# 467444_130_3_1-R1.net
KiCad netlist of a schematic drawn in Altium Designer
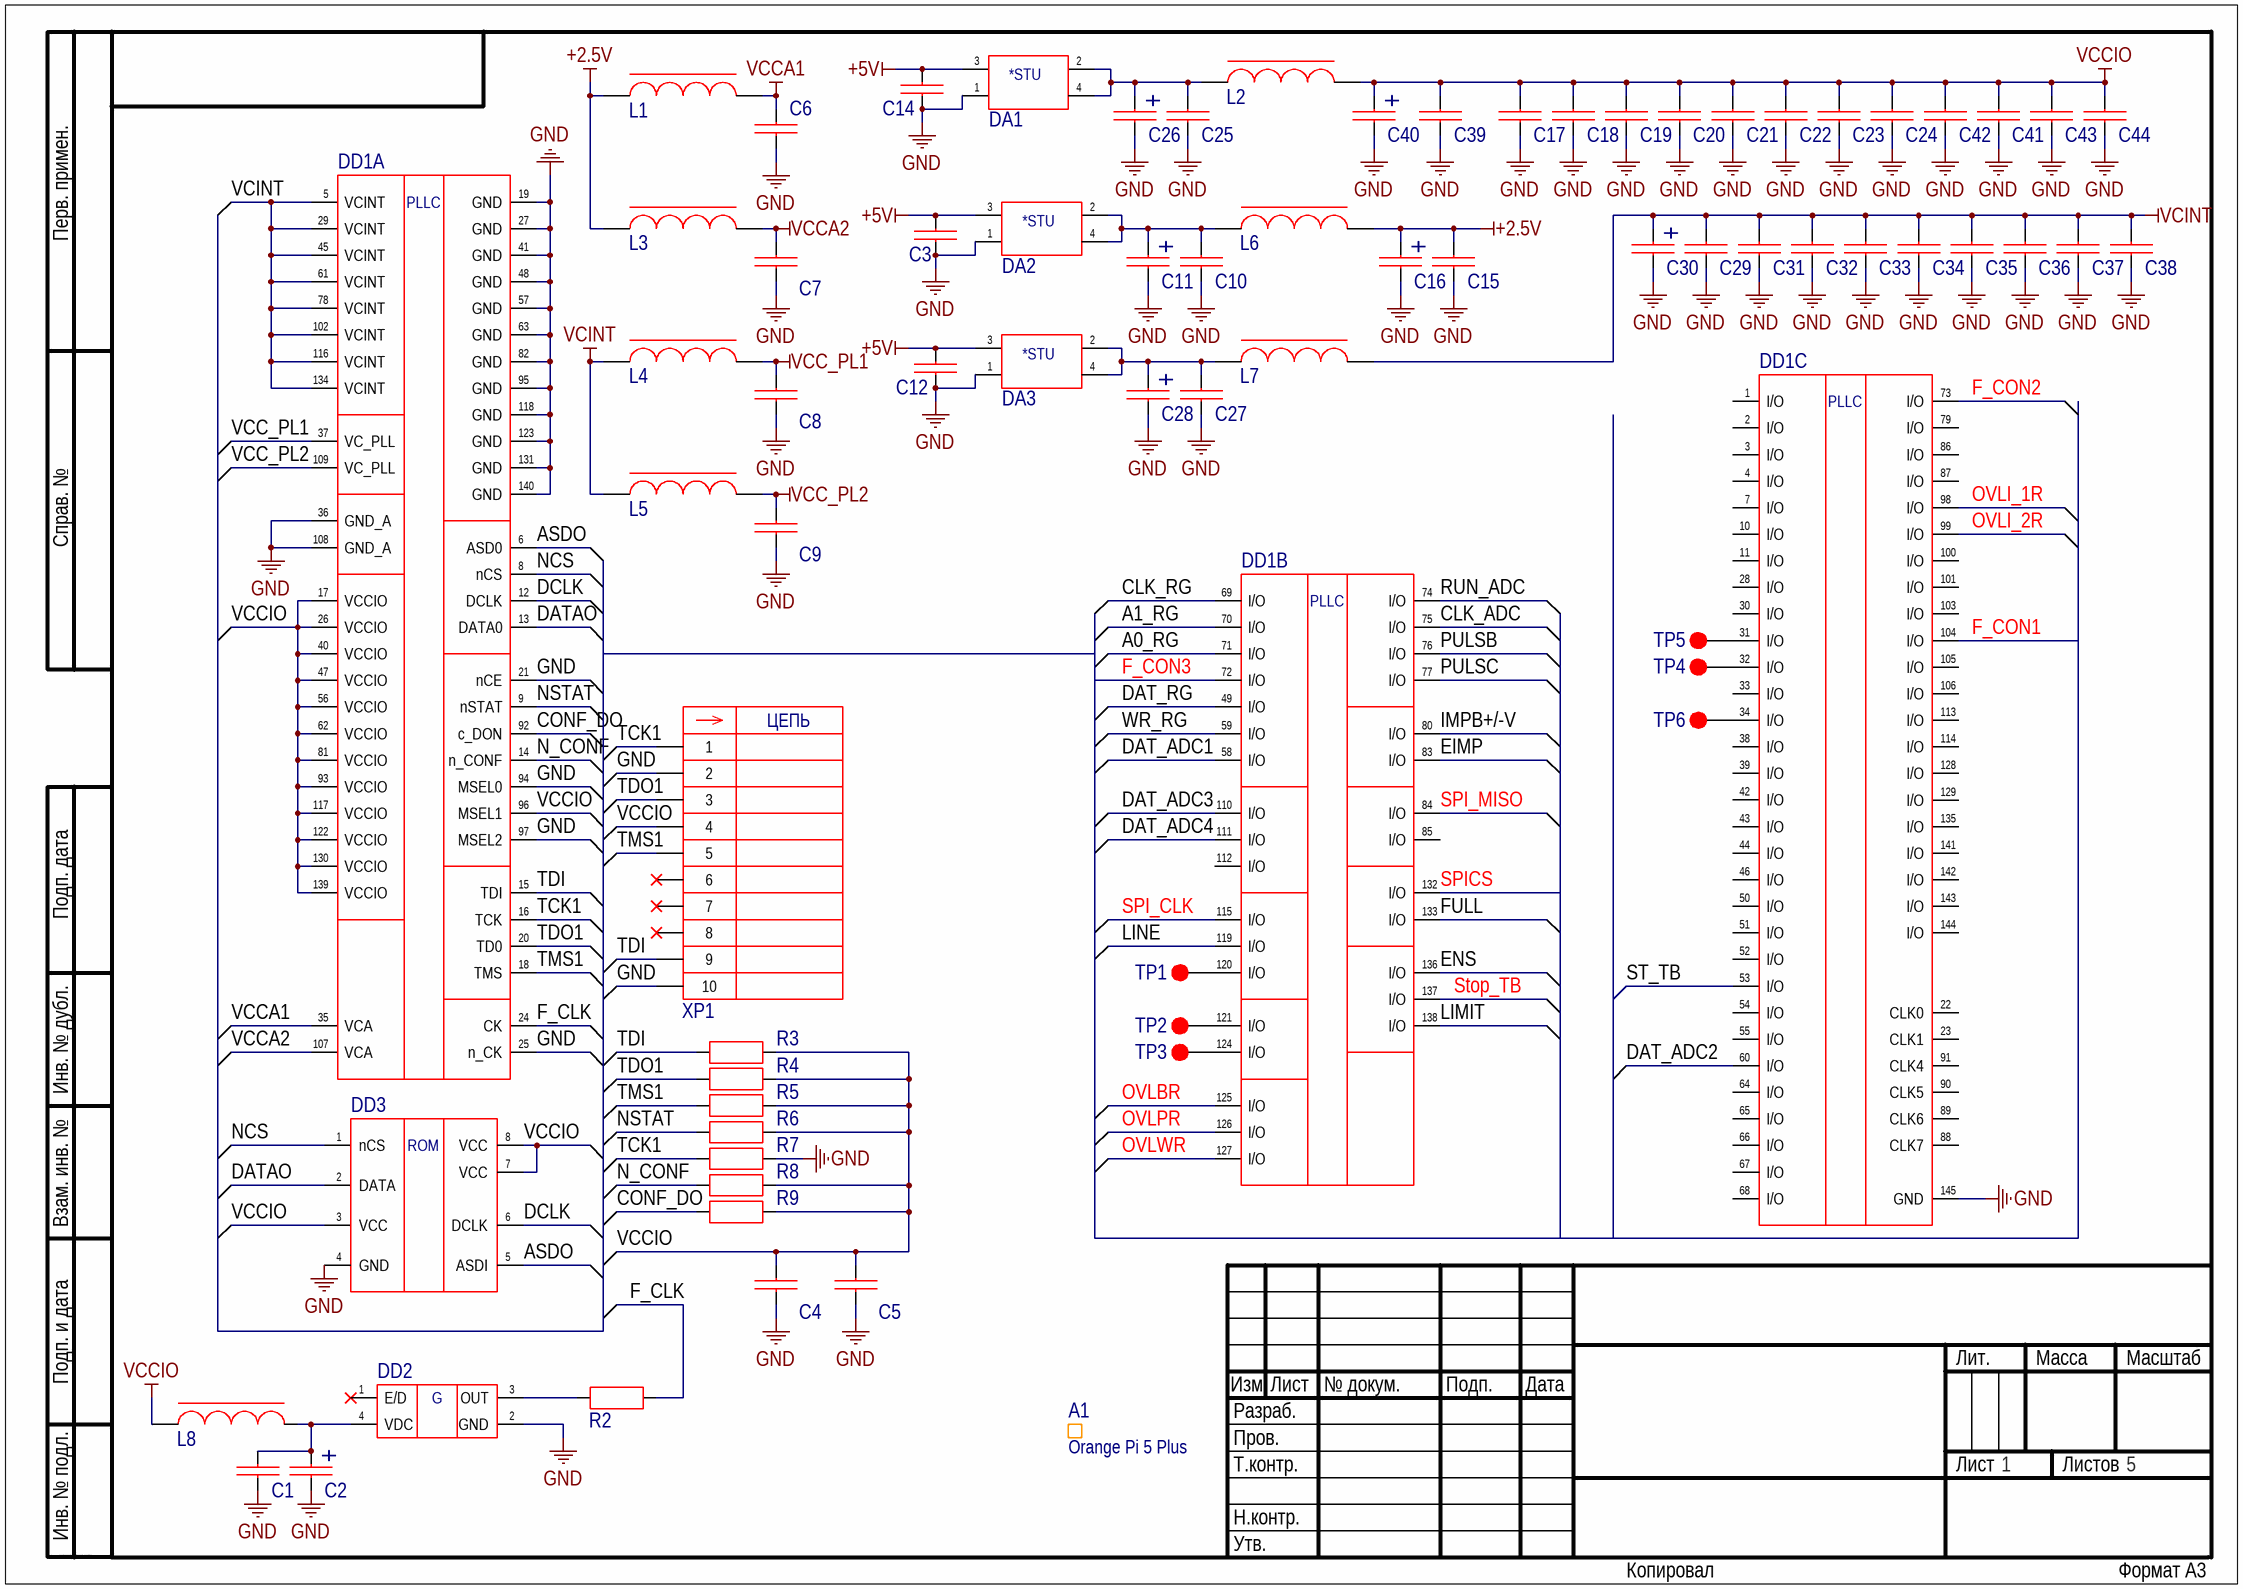
[diagram p0: УШЯИ.467444.130Э3_1-R1.SchDoc]

(export (version "E")
  (design (tool "Eeschema 10.0.6"))
  (components
    (comp (ref "A1")
      (value "Orange Pi 5 Plus")
      (footprint "Orange_Pi_5_Plus")
      (description "8GB Rockchip RK3588, HDMI 2.1, Gigabit LAN port, USB2.0/3.0, microSD card slot, USB Type-C")
      (fields (field (name "MANUFACTURER") "Orange Pi"))
      (libsource (lib "lib") (part "0"))
    )
    (comp (ref "C1")
      (value "0,1 µF")
      (footprint "C_0805 [2012 Metric]")
      (description "Неполярный конденсатор")
      (fields (field (name "MANUFACTURER") "Murata") (field (name "VOLTAGE") "50V"))
      (libsource (lib "lib") (part "C_const"))
    )
    (comp (ref "C2")
      (value "4,7 µF")
      (footprint "C+_1210 [3528-21 Metric]")
      (description "Полярный конденсатор")
      (fields (field (name "MANUFACTURER") "KYOCERA AVX") (field (name "VOLTAGE") "20V\r\n10V"))
      (libsource (lib "lib") (part "C_electrolytic"))
    )
    (comp (ref "C3")
      (value "0,1 µF")
      (footprint "C_0805 [2012 Metric]")
      (description "Неполярный конденсатор")
      (fields (field (name "MANUFACTURER") "Murata") (field (name "VOLTAGE") "50V"))
      (libsource (lib "lib") (part "C_const"))
    )
    (comp (ref "C4")
      (value "1 µF")
      (footprint "C_0805 [2012 Metric]")
      (description "Неполярный конденсатор")
      (fields (field (name "MANUFACTURER") "Murata") (field (name "VOLTAGE") "16V"))
      (libsource (lib "lib") (part "C_const"))
    )
    (comp (ref "C5")
      (value "1 µF")
      (footprint "C_0805 [2012 Metric]")
      (description "Неполярный конденсатор")
      (fields (field (name "MANUFACTURER") "Murata") (field (name "VOLTAGE") "16V"))
      (libsource (lib "lib") (part "C_const"))
    )
    (comp (ref "C6")
      (value "0,1 µF")
      (footprint "C_0805 [2012 Metric]")
      (description "Неполярный конденсатор")
      (fields (field (name "MANUFACTURER") "Murata") (field (name "VOLTAGE") "50V"))
      (libsource (lib "lib") (part "C_const"))
    )
    (comp (ref "C7")
      (value "0,1 µF")
      (footprint "C_0805 [2012 Metric]")
      (description "Неполярный конденсатор")
      (fields (field (name "MANUFACTURER") "Murata") (field (name "VOLTAGE") "50V"))
      (libsource (lib "lib") (part "C_const"))
    )
    (comp (ref "C8")
      (value "0,1 µF")
      (footprint "C_0805 [2012 Metric]")
      (description "Неполярный конденсатор")
      (fields (field (name "MANUFACTURER") "Murata") (field (name "VOLTAGE") "50V"))
      (libsource (lib "lib") (part "C_const"))
    )
    (comp (ref "C9")
      (value "0,1 µF")
      (footprint "C_0805 [2012 Metric]")
      (description "Неполярный конденсатор")
      (fields (field (name "MANUFACTURER") "Murata") (field (name "VOLTAGE") "50V"))
      (libsource (lib "lib") (part "C_const"))
    )
    (comp (ref "C10")
      (value "0,1 µF")
      (footprint "C_0805 [2012 Metric]")
      (description "Неполярный конденсатор")
      (fields (field (name "MANUFACTURER") "Murata") (field (name "VOLTAGE") "50V"))
      (libsource (lib "lib") (part "C_const"))
    )
    (comp (ref "C11")
      (value "4,7 µF")
      (footprint "C+_1210 [3528-21 Metric]")
      (description "Полярный конденсатор")
      (fields (field (name "MANUFACTURER") "KYOCERA AVX") (field (name "VOLTAGE") "20V\r\n10V"))
      (libsource (lib "lib") (part "C_electrolytic"))
    )
    (comp (ref "C12")
      (value "0,1 µF")
      (footprint "C_0805 [2012 Metric]")
      (description "Неполярный конденсатор")
      (fields (field (name "MANUFACTURER") "Murata") (field (name "VOLTAGE") "50V"))
      (libsource (lib "lib") (part "C_const"))
    )
    (comp (ref "C14")
      (value "0,1 µF")
      (footprint "C_0805 [2012 Metric]")
      (description "Неполярный конденсатор")
      (fields (field (name "MANUFACTURER") "Murata") (field (name "VOLTAGE") "50V"))
      (libsource (lib "lib") (part "C_const"))
    )
    (comp (ref "C15")
      (value "0,1 µF")
      (footprint "C_0805 [2012 Metric]")
      (description "Неполярный конденсатор")
      (fields (field (name "MANUFACTURER") "Murata") (field (name "VOLTAGE") "50V"))
      (libsource (lib "lib") (part "C_const"))
    )
    (comp (ref "C16")
      (value "10 µF")
      (footprint "C+_1210 [3528-21 Metric]")
      (description "Полярный конденсатор")
      (fields (field (name "MANUFACTURER") "KYOCERA AVX") (field (name "VOLTAGE") "20V\r\n10V"))
      (libsource (lib "lib") (part "C_electrolytic"))
    )
    (comp (ref "C17")
      (value "0,1 µF")
      (footprint "C_0805 [2012 Metric]")
      (description "Неполярный конденсатор")
      (fields (field (name "MANUFACTURER") "Murata") (field (name "VOLTAGE") "50V"))
      (libsource (lib "lib") (part "C_const"))
    )
    (comp (ref "C18")
      (value "0,1 µF")
      (footprint "C_0805 [2012 Metric]")
      (description "Неполярный конденсатор")
      (fields (field (name "MANUFACTURER") "Murata") (field (name "VOLTAGE") "50V"))
      (libsource (lib "lib") (part "C_const"))
    )
    (comp (ref "C19")
      (value "0,1 µF")
      (footprint "C_0805 [2012 Metric]")
      (description "Неполярный конденсатор")
      (fields (field (name "MANUFACTURER") "Murata") (field (name "VOLTAGE") "50V"))
      (libsource (lib "lib") (part "C_const"))
    )
    (comp (ref "C20")
      (value "0,1 µF")
      (footprint "C_0805 [2012 Metric]")
      (description "Неполярный конденсатор")
      (fields (field (name "MANUFACTURER") "Murata") (field (name "VOLTAGE") "50V"))
      (libsource (lib "lib") (part "C_const"))
    )
    (comp (ref "C21")
      (value "0,1 µF")
      (footprint "C_0805 [2012 Metric]")
      (description "Неполярный конденсатор")
      (fields (field (name "MANUFACTURER") "Murata") (field (name "VOLTAGE") "50V"))
      (libsource (lib "lib") (part "C_const"))
    )
    (comp (ref "C22")
      (value "0,1 µF")
      (footprint "C_0805 [2012 Metric]")
      (description "Неполярный конденсатор")
      (fields (field (name "MANUFACTURER") "Murata") (field (name "VOLTAGE") "50V"))
      (libsource (lib "lib") (part "C_const"))
    )
    (comp (ref "C23")
      (value "0,1 µF")
      (footprint "C_0805 [2012 Metric]")
      (description "Неполярный конденсатор")
      (fields (field (name "MANUFACTURER") "Murata") (field (name "VOLTAGE") "50V"))
      (libsource (lib "lib") (part "C_const"))
    )
    (comp (ref "C24")
      (value "0,1 µF")
      (footprint "C_0805 [2012 Metric]")
      (description "Неполярный конденсатор")
      (fields (field (name "MANUFACTURER") "Murata") (field (name "VOLTAGE") "50V"))
      (libsource (lib "lib") (part "C_const"))
    )
    (comp (ref "C25")
      (value "0,1 µF")
      (footprint "C_0805 [2012 Metric]")
      (description "Неполярный конденсатор")
      (fields (field (name "MANUFACTURER") "Murata") (field (name "VOLTAGE") "50V"))
      (libsource (lib "lib") (part "C_const"))
    )
    (comp (ref "C26")
      (value "4,7 µF")
      (footprint "C+_1210 [3528-21 Metric]")
      (description "Полярный конденсатор")
      (fields (field (name "MANUFACTURER") "KYOCERA AVX") (field (name "VOLTAGE") "20V\r\n10V"))
      (libsource (lib "lib") (part "C_electrolytic"))
    )
    (comp (ref "C27")
      (value "0,1 µF")
      (footprint "C_0805 [2012 Metric]")
      (description "Неполярный конденсатор")
      (fields (field (name "MANUFACTURER") "Murata") (field (name "VOLTAGE") "50V"))
      (libsource (lib "lib") (part "C_const"))
    )
    (comp (ref "C28")
      (value "4,7 µF")
      (footprint "C+_1210 [3528-21 Metric]")
      (description "Полярный конденсатор")
      (fields (field (name "MANUFACTURER") "KYOCERA AVX") (field (name "VOLTAGE") "20V\r\n10V"))
      (libsource (lib "lib") (part "C_electrolytic"))
    )
    (comp (ref "C29")
      (value "0,1 µF")
      (footprint "C_0805 [2012 Metric]")
      (description "Неполярный конденсатор")
      (fields (field (name "MANUFACTURER") "Murata") (field (name "VOLTAGE") "50V"))
      (libsource (lib "lib") (part "C_const"))
    )
    (comp (ref "C30")
      (value "4,7 µF")
      (footprint "C+_1210 [3528-21 Metric]")
      (description "Полярный конденсатор")
      (fields (field (name "MANUFACTURER") "KYOCERA AVX") (field (name "VOLTAGE") "20V\r\n10V"))
      (libsource (lib "lib") (part "C_electrolytic"))
    )
    (comp (ref "C31")
      (value "0,1 µF")
      (footprint "C_0805 [2012 Metric]")
      (description "Неполярный конденсатор")
      (fields (field (name "MANUFACTURER") "Murata") (field (name "VOLTAGE") "50V"))
      (libsource (lib "lib") (part "C_const"))
    )
    (comp (ref "C32")
      (value "0,1 µF")
      (footprint "C_0805 [2012 Metric]")
      (description "Неполярный конденсатор")
      (fields (field (name "MANUFACTURER") "Murata") (field (name "VOLTAGE") "50V"))
      (libsource (lib "lib") (part "C_const"))
    )
    (comp (ref "C33")
      (value "0,1 µF")
      (footprint "C_0805 [2012 Metric]")
      (description "Неполярный конденсатор")
      (fields (field (name "MANUFACTURER") "Murata") (field (name "VOLTAGE") "50V"))
      (libsource (lib "lib") (part "C_const"))
    )
    (comp (ref "C34")
      (value "0,1 µF")
      (footprint "C_0805 [2012 Metric]")
      (description "Неполярный конденсатор")
      (fields (field (name "MANUFACTURER") "Murata") (field (name "VOLTAGE") "50V"))
      (libsource (lib "lib") (part "C_const"))
    )
    (comp (ref "C35")
      (value "0,1 µF")
      (footprint "C_0805 [2012 Metric]")
      (description "Неполярный конденсатор")
      (fields (field (name "MANUFACTURER") "Murata") (field (name "VOLTAGE") "50V"))
      (libsource (lib "lib") (part "C_const"))
    )
    (comp (ref "C36")
      (value "0,1 µF")
      (footprint "C_0805 [2012 Metric]")
      (description "Неполярный конденсатор")
      (fields (field (name "MANUFACTURER") "Murata") (field (name "VOLTAGE") "50V"))
      (libsource (lib "lib") (part "C_const"))
    )
    (comp (ref "C37")
      (value "0,1 µF")
      (footprint "C_0805 [2012 Metric]")
      (description "Неполярный конденсатор")
      (fields (field (name "MANUFACTURER") "Murata") (field (name "VOLTAGE") "50V"))
      (libsource (lib "lib") (part "C_const"))
    )
    (comp (ref "C38")
      (value "0,1 µF")
      (footprint "C_0805 [2012 Metric]")
      (description "Неполярный конденсатор")
      (fields (field (name "MANUFACTURER") "Murata") (field (name "VOLTAGE") "50V"))
      (libsource (lib "lib") (part "C_const"))
    )
    (comp (ref "C39")
      (value "0,1 µF")
      (footprint "C_0805 [2012 Metric]")
      (description "Неполярный конденсатор")
      (fields (field (name "MANUFACTURER") "Murata") (field (name "VOLTAGE") "50V"))
      (libsource (lib "lib") (part "C_const"))
    )
    (comp (ref "C40")
      (value "10 µF")
      (footprint "C+_1210 [3528-21 Metric]")
      (description "Полярный конденсатор")
      (fields (field (name "MANUFACTURER") "KYOCERA AVX") (field (name "VOLTAGE") "20V\r\n10V"))
      (libsource (lib "lib") (part "C_electrolytic"))
    )
    (comp (ref "C41")
      (value "0,1 µF")
      (footprint "C_0805 [2012 Metric]")
      (description "Неполярный конденсатор")
      (fields (field (name "MANUFACTURER") "Murata") (field (name "VOLTAGE") "50V"))
      (libsource (lib "lib") (part "C_const"))
    )
    (comp (ref "C42")
      (value "0,1 µF")
      (footprint "C_0805 [2012 Metric]")
      (description "Неполярный конденсатор")
      (fields (field (name "MANUFACTURER") "Murata") (field (name "VOLTAGE") "50V"))
      (libsource (lib "lib") (part "C_const"))
    )
    (comp (ref "C43")
      (value "0,1 µF")
      (footprint "C_0805 [2012 Metric]")
      (description "Неполярный конденсатор")
      (fields (field (name "MANUFACTURER") "Murata") (field (name "VOLTAGE") "50V"))
      (libsource (lib "lib") (part "C_const"))
    )
    (comp (ref "C44")
      (value "0,1 µF")
      (footprint "C_0805 [2012 Metric]")
      (description "Неполярный конденсатор")
      (fields (field (name "MANUFACTURER") "Murata") (field (name "VOLTAGE") "50V"))
      (libsource (lib "lib") (part "C_const"))
    )
    (comp (ref "DA1")
      (value "LD1117AS33TR")
      (footprint "SOT-223")
      (description "IC, Fixed LDO Voltage Regulator, 5.3V to 10V, 1.15V Dropout, 3.3Vout, 1Aout")
      (fields (field (name "MANUFACTURER") "STMicroelectronics"))
      (libsource (lib "lib") (part "VolReg_LD1117AS33TR"))
    )
    (comp (ref "DA2")
      (value "LD1117AS25TR")
      (footprint "SOT-223")
      (description "IC, Linear Voltage Regulator, 1 Output, 1V Dropout, 2.5Vout, 1Aout")
      (fields (field (name "MANUFACTURER") "STMicroelectronics"))
      (libsource (lib "lib") (part "VolReg_LD1117AS33TR"))
    )
    (comp (ref "DA3")
      (value "LD1117AS12TR")
      (footprint "SOT-223")
      (description "IC, Fixed LDO Voltage Regulator, 1 Output, 1V Dropout, 1.2Vout, 1Aout")
      (fields (field (name "MANUFACTURER") "STMicroelectronics"))
      (libsource (lib "lib") (part "VolReg_LD1117AS33TR"))
    )
    (comp (ref "DD1")
      (value "EP3C5E144I7")
      (footprint "EQFP-144[20x20]_0.5_22x22x1.6")
      (description "IC, Cyclone III, Field Programmable Gate Array (FPGA), 	1.15V to 1.25V, 315 MHz, 94 I/O")
      (fields (field (name "MANUFACTURER") "Intel"))
      (libsource (lib "lib") (part "EP3C5E144I7"))
    )
    (comp (ref "DD2")
      (value "O 20,0-JO32-B-3.3-1-T1-LF")
      (footprint "JO32")
      (description "Crystals, Oscillators, 20 MHz")
      (fields (field (name "MANUFACTURER") "Jauch Quartz GmbH"))
      (libsource (lib "lib") (part "JO32"))
    )
    (comp (ref "DD3")
      (value "EPCS4SI8N")
      (footprint "SOIC-8_1.27_5x4x1.75")
      (description "IC, FPGA Configuration Memory, Flash, 4 Mbit, 40 MHz, JTAG, Serial")
      (fields (field (name "MANUFACTURER") "Intel"))
      (libsource (lib "lib") (part "EPCS4"))
    )
    (comp (ref "L1")
      (value "0,22 μH")
      (footprint "IND_LQH31CN")
      (fields (field (name "MANUFACTURER") "Murata") (field (name "TOLERANCE") "±20%"))
      (libsource (lib "lib") (part "IND_ferromagnetic/ferrite_core"))
    )
    (comp (ref "L2")
      (value "~")
      (footprint "IND_0805 [2012 Metric]")
      (fields (field (name "MANUFACTURER") "Vishay") (field (name "TOLERANCE") "±25%"))
      (libsource (lib "lib") (part "IND_ferromagnetic/ferrite_core"))
    )
    (comp (ref "L3")
      (value "0,22 μH")
      (footprint "IND_LQH31CN")
      (fields (field (name "MANUFACTURER") "Murata") (field (name "TOLERANCE") "±20%"))
      (libsource (lib "lib") (part "IND_ferromagnetic/ferrite_core"))
    )
    (comp (ref "L4")
      (value "0,22 μH")
      (footprint "IND_LQH31CN")
      (fields (field (name "MANUFACTURER") "Murata") (field (name "TOLERANCE") "±20%"))
      (libsource (lib "lib") (part "IND_ferromagnetic/ferrite_core"))
    )
    (comp (ref "L5")
      (value "0,22 μH")
      (footprint "IND_LQH31CN")
      (fields (field (name "MANUFACTURER") "Murata") (field (name "TOLERANCE") "±20%"))
      (libsource (lib "lib") (part "IND_ferromagnetic/ferrite_core"))
    )
    (comp (ref "L6")
      (value "~")
      (footprint "IND_0805 [2012 Metric]")
      (fields (field (name "MANUFACTURER") "Vishay") (field (name "TOLERANCE") "±25%"))
      (libsource (lib "lib") (part "IND_ferromagnetic/ferrite_core"))
    )
    (comp (ref "L7")
      (value "~")
      (footprint "IND_0805 [2012 Metric]")
      (fields (field (name "MANUFACTURER") "Vishay") (field (name "TOLERANCE") "±25%"))
      (libsource (lib "lib") (part "IND_ferromagnetic/ferrite_core"))
    )
    (comp (ref "L8")
      (value "~")
      (footprint "IND_0805 [2012 Metric]")
      (fields (field (name "MANUFACTURER") "Vishay") (field (name "TOLERANCE") "±25%"))
      (libsource (lib "lib") (part "IND_ferromagnetic/ferrite_core"))
    )
    (comp (ref "R2")
      (value "51R")
      (footprint "R_0805 [2012 Metric]")
      (fields (field (name "TOLERANCE") "±5%"))
      (libsource (lib "lib") (part "R_Const"))
    )
    (comp (ref "R3")
      (value "1k")
      (footprint "R_0805 [2012 Metric]")
      (fields (field (name "TOLERANCE") "±5%"))
      (libsource (lib "lib") (part "R_Const"))
    )
    (comp (ref "R4")
      (value "10k")
      (footprint "R_0805 [2012 Metric]")
      (fields (field (name "TOLERANCE") "±5%"))
      (libsource (lib "lib") (part "R_Const"))
    )
    (comp (ref "R5")
      (value "1k")
      (footprint "R_0805 [2012 Metric]")
      (fields (field (name "TOLERANCE") "±5%"))
      (libsource (lib "lib") (part "R_Const"))
    )
    (comp (ref "R6")
      (value "10k")
      (footprint "R_0805 [2012 Metric]")
      (fields (field (name "TOLERANCE") "±5%"))
      (libsource (lib "lib") (part "R_Const"))
    )
    (comp (ref "R7")
      (value "1k")
      (footprint "R_0805 [2012 Metric]")
      (fields (field (name "TOLERANCE") "±5%"))
      (libsource (lib "lib") (part "R_Const"))
    )
    (comp (ref "R8")
      (value "10k")
      (footprint "R_0805 [2012 Metric]")
      (fields (field (name "TOLERANCE") "±5%"))
      (libsource (lib "lib") (part "R_Const"))
    )
    (comp (ref "R9")
      (value "10k")
      (footprint "R_0805 [2012 Metric]")
      (fields (field (name "TOLERANCE") "±5%"))
      (libsource (lib "lib") (part "R_Const"))
    )
    (comp (ref "TP1") (value "~") (footprint "DSP_1.3") (libsource (lib "lib") (part "TP")))
    (comp (ref "TP2") (value "~") (footprint "DSP_1.3") (libsource (lib "lib") (part "TP")))
    (comp (ref "TP3") (value "~") (footprint "DSP_1.3") (libsource (lib "lib") (part "TP")))
    (comp (ref "TP4") (value "~") (footprint "DSP_1.3") (libsource (lib "lib") (part "TP")))
    (comp (ref "TP5") (value "~") (footprint "DSP_1.3") (libsource (lib "lib") (part "TP")))
    (comp (ref "TP6") (value "~") (footprint "DSP_1.3") (libsource (lib "lib") (part "TP")))
    (comp (ref "XP1")
      (value "PLD-10")
      (footprint "PLD-10")
      (description "Male, 10 pins, 2 rows, Vertical")
      (fields (field (name "MANUFACTURER") "Connfly electronic"))
      (libsource (lib "lib") (part "M_10"))
    )
  )
  (nets
    (net (code "1") (name "+2.5V") (class "Default")
      (node (ref "C15") (pin "2") (pinfunction "2_2") (pintype "passive"))
      (node (ref "C16") (pin "+") (pinfunction "+_+") (pintype "passive"))
      (node (ref "L1") (pin "1") (pinfunction "1_1") (pintype "passive"))
      (node (ref "L3") (pin "1") (pinfunction "1_1") (pintype "passive"))
      (node (ref "L6") (pin "2") (pinfunction "2_2") (pintype "passive"))
    )
    (net (code "2") (name "+5V") (class "Default")
      (node (ref "C12") (pin "2") (pinfunction "2_2") (pintype "passive"))
      (node (ref "C14") (pin "2") (pinfunction "2_2") (pintype "passive"))
      (node (ref "C3") (pin "2") (pinfunction "2_2") (pintype "passive"))
      (node (ref "DA1") (pin "3") (pinfunction "VIN_3") (pintype "passive"))
      (node (ref "DA2") (pin "3") (pinfunction "VIN_3") (pintype "passive"))
      (node (ref "DA3") (pin "3") (pinfunction "VIN_3") (pintype "passive"))
    )
    (net (code "3") (name "/A0_RG") (class "Default")
      (node (ref "DD1") (pin "71") (pinfunction "I/O_71") (pintype "passive"))
    )
    (net (code "4") (name "/A1_RG") (class "Default")
      (node (ref "DD1") (pin "70") (pinfunction "I/O_70") (pintype "passive"))
    )
    (net (code "5") (name "/ASDO") (class "Default")
      (node (ref "DD1") (pin "6") (pinfunction "ASD0_6") (pintype "passive"))
      (node (ref "DD3") (pin "5") (pinfunction "ASDI_5") (pintype "passive"))
    )
    (net (code "6") (name "/CLK_ADC") (class "Default")
      (node (ref "DD1") (pin "75") (pinfunction "I/O_75") (pintype "passive"))
    )
    (net (code "7") (name "/CLK_RG") (class "Default")
      (node (ref "DD1") (pin "69") (pinfunction "I/O_69") (pintype "passive"))
    )
    (net (code "8") (name "/CONF_DO") (class "Default")
      (node (ref "DD1") (pin "92") (pinfunction "c_DON_92") (pintype "passive"))
      (node (ref "R9") (pin "1") (pinfunction "1_1") (pintype "passive"))
    )
    (net (code "9") (name "/DATAO") (class "Default")
      (node (ref "DD1") (pin "13") (pinfunction "DATA0_13") (pintype "passive"))
      (node (ref "DD3") (pin "2") (pinfunction "DATA_2") (pintype "passive"))
    )
    (net (code "10") (name "/DAT_ADC1") (class "Default")
      (node (ref "DD1") (pin "58") (pinfunction "I/O_58") (pintype "passive"))
    )
    (net (code "11") (name "/DAT_ADC2") (class "Default")
      (node (ref "DD1") (pin "60") (pinfunction "I/O_60") (pintype "passive"))
    )
    (net (code "12") (name "/DAT_ADC3") (class "Default")
      (node (ref "DD1") (pin "110") (pinfunction "I/O_110") (pintype "passive"))
    )
    (net (code "13") (name "/DAT_ADC4") (class "Default")
      (node (ref "DD1") (pin "111") (pinfunction "I/O_111") (pintype "passive"))
    )
    (net (code "14") (name "/DAT_RG") (class "Default")
      (node (ref "DD1") (pin "49") (pinfunction "I/O_49") (pintype "passive"))
    )
    (net (code "15") (name "/DCLK") (class "Default")
      (node (ref "DD1") (pin "12") (pinfunction "DCLK_12") (pintype "passive"))
      (node (ref "DD3") (pin "6") (pinfunction "DCLK_6") (pintype "passive"))
    )
    (net (code "16") (name "/EIMP") (class "Default")
      (node (ref "DD1") (pin "83") (pinfunction "I/O_83") (pintype "passive"))
    )
    (net (code "17") (name "/ENS") (class "Default")
      (node (ref "DD1") (pin "136") (pinfunction "I/O_136") (pintype "passive"))
    )
    (net (code "18") (name "/FULL") (class "Default")
      (node (ref "DD1") (pin "133") (pinfunction "I/O_133") (pintype "passive"))
    )
    (net (code "19") (name "/F_CLK") (class "Default")
      (node (ref "DD1") (pin "24") (pinfunction "CK_24") (pintype "passive"))
      (node (ref "R2") (pin "2") (pinfunction "2_2") (pintype "passive"))
    )
    (net (code "20") (name "/F_CON1") (class "Default")
      (node (ref "DD1") (pin "104") (pinfunction "I/O_104") (pintype "passive"))
    )
    (net (code "21") (name "/F_CON2") (class "Default")
      (node (ref "DD1") (pin "73") (pinfunction "I/O_73") (pintype "passive"))
    )
    (net (code "22") (name "/F_CON3") (class "Default")
      (node (ref "DD1") (pin "72") (pinfunction "I/O_72") (pintype "passive"))
    )
    (net (code "23") (name "/IMPB+{slash}-V") (class "Default")
      (node (ref "DD1") (pin "80") (pinfunction "I/O_80") (pintype "passive"))
    )
    (net (code "24") (name "/LIMIT") (class "Default")
      (node (ref "DD1") (pin "138") (pinfunction "I/O_138") (pintype "passive"))
    )
    (net (code "25") (name "/LINE") (class "Default")
      (node (ref "DD1") (pin "119") (pinfunction "I/O_119") (pintype "passive"))
    )
    (net (code "26") (name "/NCS") (class "Default")
      (node (ref "DD1") (pin "8") (pinfunction "nCS_8") (pintype "passive"))
      (node (ref "DD3") (pin "1") (pinfunction "nCS_1") (pintype "passive"))
    )
    (net (code "27") (name "/NSTAT") (class "Default")
      (node (ref "DD1") (pin "9") (pinfunction "nSTAT_9") (pintype "passive"))
      (node (ref "R6") (pin "1") (pinfunction "1_1") (pintype "passive"))
    )
    (net (code "28") (name "/N_CONF") (class "Default")
      (node (ref "DD1") (pin "14") (pinfunction "n_CONF_14") (pintype "passive"))
      (node (ref "R8") (pin "1") (pinfunction "1_1") (pintype "passive"))
    )
    (net (code "29") (name "/OVLBR") (class "Default")
      (node (ref "DD1") (pin "125") (pinfunction "I/O_125") (pintype "passive"))
    )
    (net (code "30") (name "/OVLI_1R") (class "Default")
      (node (ref "DD1") (pin "98") (pinfunction "I/O_98") (pintype "passive"))
    )
    (net (code "31") (name "/OVLI_2R") (class "Default")
      (node (ref "DD1") (pin "99") (pinfunction "I/O_99") (pintype "passive"))
    )
    (net (code "32") (name "/OVLPR") (class "Default")
      (node (ref "DD1") (pin "126") (pinfunction "I/O_126") (pintype "passive"))
    )
    (net (code "33") (name "/OVLWR") (class "Default")
      (node (ref "DD1") (pin "127") (pinfunction "I/O_127") (pintype "passive"))
    )
    (net (code "34") (name "/PULSB") (class "Default")
      (node (ref "DD1") (pin "76") (pinfunction "I/O_76") (pintype "passive"))
    )
    (net (code "35") (name "/PULSC") (class "Default")
      (node (ref "DD1") (pin "77") (pinfunction "I/O_77") (pintype "passive"))
    )
    (net (code "36") (name "/RUN_ADC") (class "Default")
      (node (ref "DD1") (pin "74") (pinfunction "I/O_74") (pintype "passive"))
    )
    (net (code "37") (name "/SPICS") (class "Default")
      (node (ref "DD1") (pin "132") (pinfunction "I/O_132") (pintype "passive"))
    )
    (net (code "38") (name "/SPI_CLK") (class "Default")
      (node (ref "DD1") (pin "115") (pinfunction "I/O_115") (pintype "passive"))
    )
    (net (code "39") (name "/SPI_MISO") (class "Default")
      (node (ref "DD1") (pin "84") (pinfunction "I/O_84") (pintype "passive"))
    )
    (net (code "40") (name "/ST_TB") (class "Default")
      (node (ref "DD1") (pin "53") (pinfunction "I/O_53") (pintype "passive"))
    )
    (net (code "41") (name "/Stop_TB") (class "Default")
      (node (ref "DD1") (pin "137") (pinfunction "I/O_137") (pintype "passive"))
    )
    (net (code "42") (name "/TCK1") (class "Default")
      (node (ref "DD1") (pin "16") (pinfunction "TCK_16") (pintype "passive"))
      (node (ref "R7") (pin "1") (pinfunction "1_1") (pintype "passive"))
      (node (ref "XP1") (pin "1") (pinfunction "1_1") (pintype "passive"))
    )
    (net (code "43") (name "/TDI") (class "Default")
      (node (ref "DD1") (pin "15") (pinfunction "TDI_15") (pintype "passive"))
      (node (ref "R3") (pin "1") (pinfunction "1_1") (pintype "passive"))
      (node (ref "XP1") (pin "9") (pinfunction "9_9") (pintype "passive"))
    )
    (net (code "44") (name "/TDO1") (class "Default")
      (node (ref "DD1") (pin "20") (pinfunction "TD0_20") (pintype "passive"))
      (node (ref "R4") (pin "1") (pinfunction "1_1") (pintype "passive"))
      (node (ref "XP1") (pin "3") (pinfunction "3_3") (pintype "passive"))
    )
    (net (code "45") (name "/TMS1") (class "Default")
      (node (ref "DD1") (pin "18") (pinfunction "TMS_18") (pintype "passive"))
      (node (ref "R5") (pin "1") (pinfunction "1_1") (pintype "passive"))
      (node (ref "XP1") (pin "5") (pinfunction "5_5") (pintype "passive"))
    )
    (net (code "46") (name "/WR_RG") (class "Default")
      (node (ref "DD1") (pin "59") (pinfunction "I/O_59") (pintype "passive"))
    )
    (net (code "47") (name "GND") (class "Default")
      (node (ref "C1") (pin "1") (pinfunction "1_1") (pintype "passive"))
      (node (ref "C10") (pin "1") (pinfunction "1_1") (pintype "passive"))
      (node (ref "C11") (pin "-") (pinfunction "-_-") (pintype "passive"))
      (node (ref "C12") (pin "1") (pinfunction "1_1") (pintype "passive"))
      (node (ref "C14") (pin "1") (pinfunction "1_1") (pintype "passive"))
      (node (ref "C15") (pin "1") (pinfunction "1_1") (pintype "passive"))
      (node (ref "C16") (pin "-") (pinfunction "-_-") (pintype "passive"))
      (node (ref "C17") (pin "1") (pinfunction "1_1") (pintype "passive"))
      (node (ref "C18") (pin "1") (pinfunction "1_1") (pintype "passive"))
      (node (ref "C19") (pin "1") (pinfunction "1_1") (pintype "passive"))
      (node (ref "C2") (pin "-") (pinfunction "-_-") (pintype "passive"))
      (node (ref "C20") (pin "1") (pinfunction "1_1") (pintype "passive"))
      (node (ref "C21") (pin "1") (pinfunction "1_1") (pintype "passive"))
      (node (ref "C22") (pin "1") (pinfunction "1_1") (pintype "passive"))
      (node (ref "C23") (pin "1") (pinfunction "1_1") (pintype "passive"))
      (node (ref "C24") (pin "1") (pinfunction "1_1") (pintype "passive"))
      (node (ref "C25") (pin "1") (pinfunction "1_1") (pintype "passive"))
      (node (ref "C26") (pin "-") (pinfunction "-_-") (pintype "passive"))
      (node (ref "C27") (pin "1") (pinfunction "1_1") (pintype "passive"))
      (node (ref "C28") (pin "-") (pinfunction "-_-") (pintype "passive"))
      (node (ref "C29") (pin "1") (pinfunction "1_1") (pintype "passive"))
      (node (ref "C3") (pin "1") (pinfunction "1_1") (pintype "passive"))
      (node (ref "C30") (pin "-") (pinfunction "-_-") (pintype "passive"))
      (node (ref "C31") (pin "1") (pinfunction "1_1") (pintype "passive"))
      (node (ref "C32") (pin "1") (pinfunction "1_1") (pintype "passive"))
      (node (ref "C33") (pin "1") (pinfunction "1_1") (pintype "passive"))
      (node (ref "C34") (pin "1") (pinfunction "1_1") (pintype "passive"))
      (node (ref "C35") (pin "1") (pinfunction "1_1") (pintype "passive"))
      (node (ref "C36") (pin "1") (pinfunction "1_1") (pintype "passive"))
      (node (ref "C37") (pin "1") (pinfunction "1_1") (pintype "passive"))
      (node (ref "C38") (pin "1") (pinfunction "1_1") (pintype "passive"))
      (node (ref "C39") (pin "1") (pinfunction "1_1") (pintype "passive"))
      (node (ref "C4") (pin "1") (pinfunction "1_1") (pintype "passive"))
      (node (ref "C40") (pin "-") (pinfunction "-_-") (pintype "passive"))
      (node (ref "C41") (pin "1") (pinfunction "1_1") (pintype "passive"))
      (node (ref "C42") (pin "1") (pinfunction "1_1") (pintype "passive"))
      (node (ref "C43") (pin "1") (pinfunction "1_1") (pintype "passive"))
      (node (ref "C44") (pin "1") (pinfunction "1_1") (pintype "passive"))
      (node (ref "C5") (pin "1") (pinfunction "1_1") (pintype "passive"))
      (node (ref "C6") (pin "1") (pinfunction "1_1") (pintype "passive"))
      (node (ref "C7") (pin "1") (pinfunction "1_1") (pintype "passive"))
      (node (ref "C8") (pin "1") (pinfunction "1_1") (pintype "passive"))
      (node (ref "C9") (pin "1") (pinfunction "1_1") (pintype "passive"))
      (node (ref "DA1") (pin "1") (pinfunction "ADJ/GND_1") (pintype "passive"))
      (node (ref "DA2") (pin "1") (pinfunction "ADJ/GND_1") (pintype "passive"))
      (node (ref "DA3") (pin "1") (pinfunction "ADJ/GND_1") (pintype "passive"))
      (node (ref "DD1") (pin "108") (pinfunction "GND_A_108") (pintype "passive"))
      (node (ref "DD1") (pin "118") (pinfunction "GND_118") (pintype "passive"))
      (node (ref "DD1") (pin "123") (pinfunction "GND_123") (pintype "passive"))
      (node (ref "DD1") (pin "131") (pinfunction "GND_131") (pintype "passive"))
      (node (ref "DD1") (pin "140") (pinfunction "GND_140") (pintype "passive"))
      (node (ref "DD1") (pin "145") (pinfunction "GND_145") (pintype "passive"))
      (node (ref "DD1") (pin "19") (pinfunction "GND_19") (pintype "passive"))
      (node (ref "DD1") (pin "21") (pinfunction "nCE_21") (pintype "passive"))
      (node (ref "DD1") (pin "25") (pinfunction "n_CK_25") (pintype "passive"))
      (node (ref "DD1") (pin "27") (pinfunction "GND_27") (pintype "passive"))
      (node (ref "DD1") (pin "36") (pinfunction "GND_A_36") (pintype "passive"))
      (node (ref "DD1") (pin "41") (pinfunction "GND_41") (pintype "passive"))
      (node (ref "DD1") (pin "48") (pinfunction "GND_48") (pintype "passive"))
      (node (ref "DD1") (pin "57") (pinfunction "GND_57") (pintype "passive"))
      (node (ref "DD1") (pin "63") (pinfunction "GND_63") (pintype "passive"))
      (node (ref "DD1") (pin "82") (pinfunction "GND_82") (pintype "passive"))
      (node (ref "DD1") (pin "94") (pinfunction "MSEL0_94") (pintype "passive"))
      (node (ref "DD1") (pin "95") (pinfunction "GND_95") (pintype "passive"))
      (node (ref "DD1") (pin "97") (pinfunction "MSEL2_97") (pintype "passive"))
      (node (ref "DD2") (pin "2") (pinfunction "GND_2") (pintype "passive"))
      (node (ref "DD3") (pin "4") (pinfunction "GND_4") (pintype "passive"))
      (node (ref "R7") (pin "2") (pinfunction "2_2") (pintype "passive"))
      (node (ref "XP1") (pin "10") (pinfunction "10_10") (pintype "passive"))
      (node (ref "XP1") (pin "2") (pinfunction "2_2") (pintype "passive"))
    )
    (net (code "48") (name "Net-(C10-Pad2)") (class "Default")
      (node (ref "C10") (pin "2") (pinfunction "2_2") (pintype "passive"))
      (node (ref "C11") (pin "+") (pinfunction "+_+") (pintype "passive"))
      (node (ref "DA2") (pin "2") (pinfunction "VOUT_2") (pintype "passive"))
      (node (ref "DA2") (pin "4") (pinfunction "VOUT_4") (pintype "passive"))
      (node (ref "L6") (pin "1") (pinfunction "1_1") (pintype "passive"))
    )
    (net (code "49") (name "Net-(C25-Pad2)") (class "Default")
      (node (ref "C25") (pin "2") (pinfunction "2_2") (pintype "passive"))
      (node (ref "C26") (pin "+") (pinfunction "+_+") (pintype "passive"))
      (node (ref "DA1") (pin "2") (pinfunction "VOUT_2") (pintype "passive"))
      (node (ref "DA1") (pin "4") (pinfunction "VOUT_4") (pintype "passive"))
      (node (ref "L2") (pin "1") (pinfunction "1_1") (pintype "passive"))
    )
    (net (code "50") (name "Net-(C27-Pad2)") (class "Default")
      (node (ref "C27") (pin "2") (pinfunction "2_2") (pintype "passive"))
      (node (ref "C28") (pin "+") (pinfunction "+_+") (pintype "passive"))
      (node (ref "DA3") (pin "2") (pinfunction "VOUT_2") (pintype "passive"))
      (node (ref "DA3") (pin "4") (pinfunction "VOUT_4") (pintype "passive"))
      (node (ref "L7") (pin "1") (pinfunction "1_1") (pintype "passive"))
    )
    (net (code "51") (name "Net-(DD1B-I{slash}O-Pad120)") (class "Default")
      (node (ref "DD1") (pin "120") (pinfunction "I/O_120") (pintype "passive"))
      (node (ref "TP1") (pin "1") (pinfunction "1_1") (pintype "passive"))
    )
    (net (code "52") (name "Net-(DD1B-I{slash}O-Pad121)") (class "Default")
      (node (ref "DD1") (pin "121") (pinfunction "I/O_121") (pintype "passive"))
      (node (ref "TP2") (pin "1") (pinfunction "1_1") (pintype "passive"))
    )
    (net (code "53") (name "Net-(DD1B-I{slash}O-Pad124)") (class "Default")
      (node (ref "DD1") (pin "124") (pinfunction "I/O_124") (pintype "passive"))
      (node (ref "TP3") (pin "1") (pinfunction "1_1") (pintype "passive"))
    )
    (net (code "54") (name "Net-(DD1C-I{slash}O-Pad31)") (class "Default")
      (node (ref "DD1") (pin "31") (pinfunction "I/O_31") (pintype "passive"))
      (node (ref "TP5") (pin "1") (pinfunction "1_1") (pintype "passive"))
    )
    (net (code "55") (name "Net-(DD1C-I{slash}O-Pad32)") (class "Default")
      (node (ref "DD1") (pin "32") (pinfunction "I/O_32") (pintype "passive"))
      (node (ref "TP4") (pin "1") (pinfunction "1_1") (pintype "passive"))
    )
    (net (code "56") (name "Net-(DD1C-I{slash}O-Pad34)") (class "Default")
      (node (ref "DD1") (pin "34") (pinfunction "I/O_34") (pintype "passive"))
      (node (ref "TP6") (pin "1") (pinfunction "1_1") (pintype "passive"))
    )
    (net (code "57") (name "Net-(DD2-OUT)") (class "Default")
      (node (ref "DD2") (pin "3") (pinfunction "OUT_3") (pintype "passive"))
      (node (ref "R2") (pin "1") (pinfunction "1_1") (pintype "passive"))
    )
    (net (code "58") (name "Net-(DD2-VDC)") (class "Default")
      (node (ref "C1") (pin "2") (pinfunction "2_2") (pintype "passive"))
      (node (ref "C2") (pin "+") (pinfunction "+_+") (pintype "passive"))
      (node (ref "DD2") (pin "4") (pinfunction "VDC_4") (pintype "passive"))
      (node (ref "L8") (pin "2") (pinfunction "2_2") (pintype "passive"))
    )
    (net (code "59") (name "VCCA1") (class "Default")
      (node (ref "C6") (pin "2") (pinfunction "2_2") (pintype "passive"))
      (node (ref "DD1") (pin "35") (pinfunction "VCA_35") (pintype "passive"))
      (node (ref "L1") (pin "2") (pinfunction "2_2") (pintype "passive"))
    )
    (net (code "60") (name "VCCA2") (class "Default")
      (node (ref "C7") (pin "2") (pinfunction "2_2") (pintype "passive"))
      (node (ref "DD1") (pin "107") (pinfunction "VCA_107") (pintype "passive"))
      (node (ref "L3") (pin "2") (pinfunction "2_2") (pintype "passive"))
    )
    (net (code "61") (name "VCCIO") (class "Default")
      (node (ref "C17") (pin "2") (pinfunction "2_2") (pintype "passive"))
      (node (ref "C18") (pin "2") (pinfunction "2_2") (pintype "passive"))
      (node (ref "C19") (pin "2") (pinfunction "2_2") (pintype "passive"))
      (node (ref "C20") (pin "2") (pinfunction "2_2") (pintype "passive"))
      (node (ref "C21") (pin "2") (pinfunction "2_2") (pintype "passive"))
      (node (ref "C22") (pin "2") (pinfunction "2_2") (pintype "passive"))
      (node (ref "C23") (pin "2") (pinfunction "2_2") (pintype "passive"))
      (node (ref "C24") (pin "2") (pinfunction "2_2") (pintype "passive"))
      (node (ref "C39") (pin "2") (pinfunction "2_2") (pintype "passive"))
      (node (ref "C4") (pin "2") (pinfunction "2_2") (pintype "passive"))
      (node (ref "C40") (pin "+") (pinfunction "+_+") (pintype "passive"))
      (node (ref "C41") (pin "2") (pinfunction "2_2") (pintype "passive"))
      (node (ref "C42") (pin "2") (pinfunction "2_2") (pintype "passive"))
      (node (ref "C43") (pin "2") (pinfunction "2_2") (pintype "passive"))
      (node (ref "C44") (pin "2") (pinfunction "2_2") (pintype "passive"))
      (node (ref "C5") (pin "2") (pinfunction "2_2") (pintype "passive"))
      (node (ref "DD1") (pin "117") (pinfunction "VCCIO_117") (pintype "passive"))
      (node (ref "DD1") (pin "122") (pinfunction "VCCIO_122") (pintype "passive"))
      (node (ref "DD1") (pin "130") (pinfunction "VCCIO_130") (pintype "passive"))
      (node (ref "DD1") (pin "139") (pinfunction "VCCIO_139") (pintype "passive"))
      (node (ref "DD1") (pin "17") (pinfunction "VCCIO_17") (pintype "passive"))
      (node (ref "DD1") (pin "26") (pinfunction "VCCIO_26") (pintype "passive"))
      (node (ref "DD1") (pin "40") (pinfunction "VCCIO_40") (pintype "passive"))
      (node (ref "DD1") (pin "47") (pinfunction "VCCIO_47") (pintype "passive"))
      (node (ref "DD1") (pin "56") (pinfunction "VCCIO_56") (pintype "passive"))
      (node (ref "DD1") (pin "62") (pinfunction "VCCIO_62") (pintype "passive"))
      (node (ref "DD1") (pin "81") (pinfunction "VCCIO_81") (pintype "passive"))
      (node (ref "DD1") (pin "93") (pinfunction "VCCIO_93") (pintype "passive"))
      (node (ref "DD1") (pin "96") (pinfunction "MSEL1_96") (pintype "passive"))
      (node (ref "DD3") (pin "3") (pinfunction "VCC_3") (pintype "passive"))
      (node (ref "DD3") (pin "7") (pinfunction "VCC_7") (pintype "passive"))
      (node (ref "DD3") (pin "8") (pinfunction "VCC_8") (pintype "passive"))
      (node (ref "L2") (pin "2") (pinfunction "2_2") (pintype "passive"))
      (node (ref "L8") (pin "1") (pinfunction "1_1") (pintype "passive"))
      (node (ref "R3") (pin "2") (pinfunction "2_2") (pintype "passive"))
      (node (ref "R4") (pin "2") (pinfunction "2_2") (pintype "passive"))
      (node (ref "R5") (pin "2") (pinfunction "2_2") (pintype "passive"))
      (node (ref "R6") (pin "2") (pinfunction "2_2") (pintype "passive"))
      (node (ref "R8") (pin "2") (pinfunction "2_2") (pintype "passive"))
      (node (ref "R9") (pin "2") (pinfunction "2_2") (pintype "passive"))
      (node (ref "XP1") (pin "4") (pinfunction "4_4") (pintype "passive"))
    )
    (net (code "62") (name "VCC_PL1") (class "Default")
      (node (ref "C8") (pin "2") (pinfunction "2_2") (pintype "passive"))
      (node (ref "DD1") (pin "37") (pinfunction "VC_PLL_37") (pintype "passive"))
      (node (ref "L4") (pin "2") (pinfunction "2_2") (pintype "passive"))
    )
    (net (code "63") (name "VCC_PL2") (class "Default")
      (node (ref "C9") (pin "2") (pinfunction "2_2") (pintype "passive"))
      (node (ref "DD1") (pin "109") (pinfunction "VC_PLL_109") (pintype "passive"))
      (node (ref "L5") (pin "2") (pinfunction "2_2") (pintype "passive"))
    )
    (net (code "64") (name "VCINT") (class "Default")
      (node (ref "C29") (pin "2") (pinfunction "2_2") (pintype "passive"))
      (node (ref "C30") (pin "+") (pinfunction "+_+") (pintype "passive"))
      (node (ref "C31") (pin "2") (pinfunction "2_2") (pintype "passive"))
      (node (ref "C32") (pin "2") (pinfunction "2_2") (pintype "passive"))
      (node (ref "C33") (pin "2") (pinfunction "2_2") (pintype "passive"))
      (node (ref "C34") (pin "2") (pinfunction "2_2") (pintype "passive"))
      (node (ref "C35") (pin "2") (pinfunction "2_2") (pintype "passive"))
      (node (ref "C36") (pin "2") (pinfunction "2_2") (pintype "passive"))
      (node (ref "C37") (pin "2") (pinfunction "2_2") (pintype "passive"))
      (node (ref "C38") (pin "2") (pinfunction "2_2") (pintype "passive"))
      (node (ref "DD1") (pin "102") (pinfunction "VCINT_102") (pintype "passive"))
      (node (ref "DD1") (pin "116") (pinfunction "VCINT_116") (pintype "passive"))
      (node (ref "DD1") (pin "134") (pinfunction "VCINT_134") (pintype "passive"))
      (node (ref "DD1") (pin "29") (pinfunction "VCINT_29") (pintype "passive"))
      (node (ref "DD1") (pin "45") (pinfunction "VCINT_45") (pintype "passive"))
      (node (ref "DD1") (pin "5") (pinfunction "VCINT_5") (pintype "passive"))
      (node (ref "DD1") (pin "61") (pinfunction "VCINT_61") (pintype "passive"))
      (node (ref "DD1") (pin "78") (pinfunction "VCINT_78") (pintype "passive"))
      (node (ref "L4") (pin "1") (pinfunction "1_1") (pintype "passive"))
      (node (ref "L5") (pin "1") (pinfunction "1_1") (pintype "passive"))
      (node (ref "L7") (pin "2") (pinfunction "2_2") (pintype "passive"))
    )
    (net (code "65") (name "unconnected-(DD1B-I{slash}O-Pad85)") (class "Default")
      (node (ref "DD1") (pin "85") (pinfunction "I/O_85") (pintype "passive"))
    )
    (net (code "66") (name "unconnected-(DD1B-I{slash}O-Pad112)") (class "Default")
      (node (ref "DD1") (pin "112") (pinfunction "I/O_112") (pintype "passive"))
    )
    (net (code "67") (name "unconnected-(DD1C-CLK0-Pad22)") (class "Default")
      (node (ref "DD1") (pin "22") (pinfunction "CLK0_22") (pintype "passive"))
    )
    (net (code "68") (name "unconnected-(DD1C-CLK1-Pad23)") (class "Default")
      (node (ref "DD1") (pin "23") (pinfunction "CLK1_23") (pintype "passive"))
    )
    (net (code "69") (name "unconnected-(DD1C-CLK4-Pad91)") (class "Default")
      (node (ref "DD1") (pin "91") (pinfunction "CLK4_91") (pintype "passive"))
    )
    (net (code "70") (name "unconnected-(DD1C-CLK5-Pad90)") (class "Default")
      (node (ref "DD1") (pin "90") (pinfunction "CLK5_90") (pintype "passive"))
    )
    (net (code "71") (name "unconnected-(DD1C-CLK6-Pad89)") (class "Default")
      (node (ref "DD1") (pin "89") (pinfunction "CLK6_89") (pintype "passive"))
    )
    (net (code "72") (name "unconnected-(DD1C-CLK7-Pad88)") (class "Default")
      (node (ref "DD1") (pin "88") (pinfunction "CLK7_88") (pintype "passive"))
    )
    (net (code "73") (name "unconnected-(DD1C-I{slash}O-Pad1)") (class "Default")
      (node (ref "DD1") (pin "1") (pinfunction "I/O_1") (pintype "passive"))
    )
    (net (code "74") (name "unconnected-(DD1C-I{slash}O-Pad2)") (class "Default")
      (node (ref "DD1") (pin "2") (pinfunction "I/O_2") (pintype "passive"))
    )
    (net (code "75") (name "unconnected-(DD1C-I{slash}O-Pad3)") (class "Default")
      (node (ref "DD1") (pin "3") (pinfunction "I/O_3") (pintype "passive"))
    )
    (net (code "76") (name "unconnected-(DD1C-I{slash}O-Pad4)") (class "Default")
      (node (ref "DD1") (pin "4") (pinfunction "I/O_4") (pintype "passive"))
    )
    (net (code "77") (name "unconnected-(DD1C-I{slash}O-Pad7)") (class "Default")
      (node (ref "DD1") (pin "7") (pinfunction "I/O_7") (pintype "passive"))
    )
    (net (code "78") (name "unconnected-(DD1C-I{slash}O-Pad10)") (class "Default")
      (node (ref "DD1") (pin "10") (pinfunction "I/O_10") (pintype "passive"))
    )
    (net (code "79") (name "unconnected-(DD1C-I{slash}O-Pad11)") (class "Default")
      (node (ref "DD1") (pin "11") (pinfunction "I/O_11") (pintype "passive"))
    )
    (net (code "80") (name "unconnected-(DD1C-I{slash}O-Pad28)") (class "Default")
      (node (ref "DD1") (pin "28") (pinfunction "I/O_28") (pintype "passive"))
    )
    (net (code "81") (name "unconnected-(DD1C-I{slash}O-Pad30)") (class "Default")
      (node (ref "DD1") (pin "30") (pinfunction "I/O_30") (pintype "passive"))
    )
    (net (code "82") (name "unconnected-(DD1C-I{slash}O-Pad33)") (class "Default")
      (node (ref "DD1") (pin "33") (pinfunction "I/O_33") (pintype "passive"))
    )
    (net (code "83") (name "unconnected-(DD1C-I{slash}O-Pad38)") (class "Default")
      (node (ref "DD1") (pin "38") (pinfunction "I/O_38") (pintype "passive"))
    )
    (net (code "84") (name "unconnected-(DD1C-I{slash}O-Pad39)") (class "Default")
      (node (ref "DD1") (pin "39") (pinfunction "I/O_39") (pintype "passive"))
    )
    (net (code "85") (name "unconnected-(DD1C-I{slash}O-Pad42)") (class "Default")
      (node (ref "DD1") (pin "42") (pinfunction "I/O_42") (pintype "passive"))
    )
    (net (code "86") (name "unconnected-(DD1C-I{slash}O-Pad43)") (class "Default")
      (node (ref "DD1") (pin "43") (pinfunction "I/O_43") (pintype "passive"))
    )
    (net (code "87") (name "unconnected-(DD1C-I{slash}O-Pad44)") (class "Default")
      (node (ref "DD1") (pin "44") (pinfunction "I/O_44") (pintype "passive"))
    )
    (net (code "88") (name "unconnected-(DD1C-I{slash}O-Pad46)") (class "Default")
      (node (ref "DD1") (pin "46") (pinfunction "I/O_46") (pintype "passive"))
    )
    (net (code "89") (name "unconnected-(DD1C-I{slash}O-Pad50)") (class "Default")
      (node (ref "DD1") (pin "50") (pinfunction "I/O_50") (pintype "passive"))
    )
    (net (code "90") (name "unconnected-(DD1C-I{slash}O-Pad51)") (class "Default")
      (node (ref "DD1") (pin "51") (pinfunction "I/O_51") (pintype "passive"))
    )
    (net (code "91") (name "unconnected-(DD1C-I{slash}O-Pad52)") (class "Default")
      (node (ref "DD1") (pin "52") (pinfunction "I/O_52") (pintype "passive"))
    )
    (net (code "92") (name "unconnected-(DD1C-I{slash}O-Pad54)") (class "Default")
      (node (ref "DD1") (pin "54") (pinfunction "I/O_54") (pintype "passive"))
    )
    (net (code "93") (name "unconnected-(DD1C-I{slash}O-Pad55)") (class "Default")
      (node (ref "DD1") (pin "55") (pinfunction "I/O_55") (pintype "passive"))
    )
    (net (code "94") (name "unconnected-(DD1C-I{slash}O-Pad64)") (class "Default")
      (node (ref "DD1") (pin "64") (pinfunction "I/O_64") (pintype "passive"))
    )
    (net (code "95") (name "unconnected-(DD1C-I{slash}O-Pad65)") (class "Default")
      (node (ref "DD1") (pin "65") (pinfunction "I/O_65") (pintype "passive"))
    )
    (net (code "96") (name "unconnected-(DD1C-I{slash}O-Pad66)") (class "Default")
      (node (ref "DD1") (pin "66") (pinfunction "I/O_66") (pintype "passive"))
    )
    (net (code "97") (name "unconnected-(DD1C-I{slash}O-Pad67)") (class "Default")
      (node (ref "DD1") (pin "67") (pinfunction "I/O_67") (pintype "passive"))
    )
    (net (code "98") (name "unconnected-(DD1C-I{slash}O-Pad68)") (class "Default")
      (node (ref "DD1") (pin "68") (pinfunction "I/O_68") (pintype "passive"))
    )
    (net (code "99") (name "unconnected-(DD1C-I{slash}O-Pad79)") (class "Default")
      (node (ref "DD1") (pin "79") (pinfunction "I/O_79") (pintype "passive"))
    )
    (net (code "100") (name "unconnected-(DD1C-I{slash}O-Pad86)") (class "Default")
      (node (ref "DD1") (pin "86") (pinfunction "I/O_86") (pintype "passive"))
    )
    (net (code "101") (name "unconnected-(DD1C-I{slash}O-Pad87)") (class "Default")
      (node (ref "DD1") (pin "87") (pinfunction "I/O_87") (pintype "passive"))
    )
    (net (code "102") (name "unconnected-(DD1C-I{slash}O-Pad100)") (class "Default")
      (node (ref "DD1") (pin "100") (pinfunction "I/O_100") (pintype "passive"))
    )
    (net (code "103") (name "unconnected-(DD1C-I{slash}O-Pad101)") (class "Default")
      (node (ref "DD1") (pin "101") (pinfunction "I/O_101") (pintype "passive"))
    )
    (net (code "104") (name "unconnected-(DD1C-I{slash}O-Pad103)") (class "Default")
      (node (ref "DD1") (pin "103") (pinfunction "I/O_103") (pintype "passive"))
    )
    (net (code "105") (name "unconnected-(DD1C-I{slash}O-Pad105)") (class "Default")
      (node (ref "DD1") (pin "105") (pinfunction "I/O_105") (pintype "passive"))
    )
    (net (code "106") (name "unconnected-(DD1C-I{slash}O-Pad106)") (class "Default")
      (node (ref "DD1") (pin "106") (pinfunction "I/O_106") (pintype "passive"))
    )
    (net (code "107") (name "unconnected-(DD1C-I{slash}O-Pad113)") (class "Default")
      (node (ref "DD1") (pin "113") (pinfunction "I/O_113") (pintype "passive"))
    )
    (net (code "108") (name "unconnected-(DD1C-I{slash}O-Pad114)") (class "Default")
      (node (ref "DD1") (pin "114") (pinfunction "I/O_114") (pintype "passive"))
    )
    (net (code "109") (name "unconnected-(DD1C-I{slash}O-Pad128)") (class "Default")
      (node (ref "DD1") (pin "128") (pinfunction "I/O_128") (pintype "passive"))
    )
    (net (code "110") (name "unconnected-(DD1C-I{slash}O-Pad129)") (class "Default")
      (node (ref "DD1") (pin "129") (pinfunction "I/O_129") (pintype "passive"))
    )
    (net (code "111") (name "unconnected-(DD1C-I{slash}O-Pad135)") (class "Default")
      (node (ref "DD1") (pin "135") (pinfunction "I/O_135") (pintype "passive"))
    )
    (net (code "112") (name "unconnected-(DD1C-I{slash}O-Pad141)") (class "Default")
      (node (ref "DD1") (pin "141") (pinfunction "I/O_141") (pintype "passive"))
    )
    (net (code "113") (name "unconnected-(DD1C-I{slash}O-Pad142)") (class "Default")
      (node (ref "DD1") (pin "142") (pinfunction "I/O_142") (pintype "passive"))
    )
    (net (code "114") (name "unconnected-(DD1C-I{slash}O-Pad143)") (class "Default")
      (node (ref "DD1") (pin "143") (pinfunction "I/O_143") (pintype "passive"))
    )
    (net (code "115") (name "unconnected-(DD1C-I{slash}O-Pad144)") (class "Default")
      (node (ref "DD1") (pin "144") (pinfunction "I/O_144") (pintype "passive"))
    )
    (net (code "116") (name "unconnected-(DD2-E{slash}D-Pad1)") (class "Default")
      (node (ref "DD2") (pin "1") (pinfunction "E/D_1") (pintype "passive+no_connect"))
    )
    (net (code "117") (name "unconnected-(XP1-Pad6)") (class "Default")
      (node (ref "XP1") (pin "6") (pinfunction "6_6") (pintype "passive+no_connect"))
    )
    (net (code "118") (name "unconnected-(XP1-Pad7)") (class "Default")
      (node (ref "XP1") (pin "7") (pinfunction "7_7") (pintype "passive+no_connect"))
    )
    (net (code "119") (name "unconnected-(XP1-Pad8)") (class "Default")
      (node (ref "XP1") (pin "8") (pinfunction "8_8") (pintype "passive+no_connect"))
    )
  )
)
